# 3_InfoPerif.net
KiCad netlist of a schematic drawn in Altium Designer
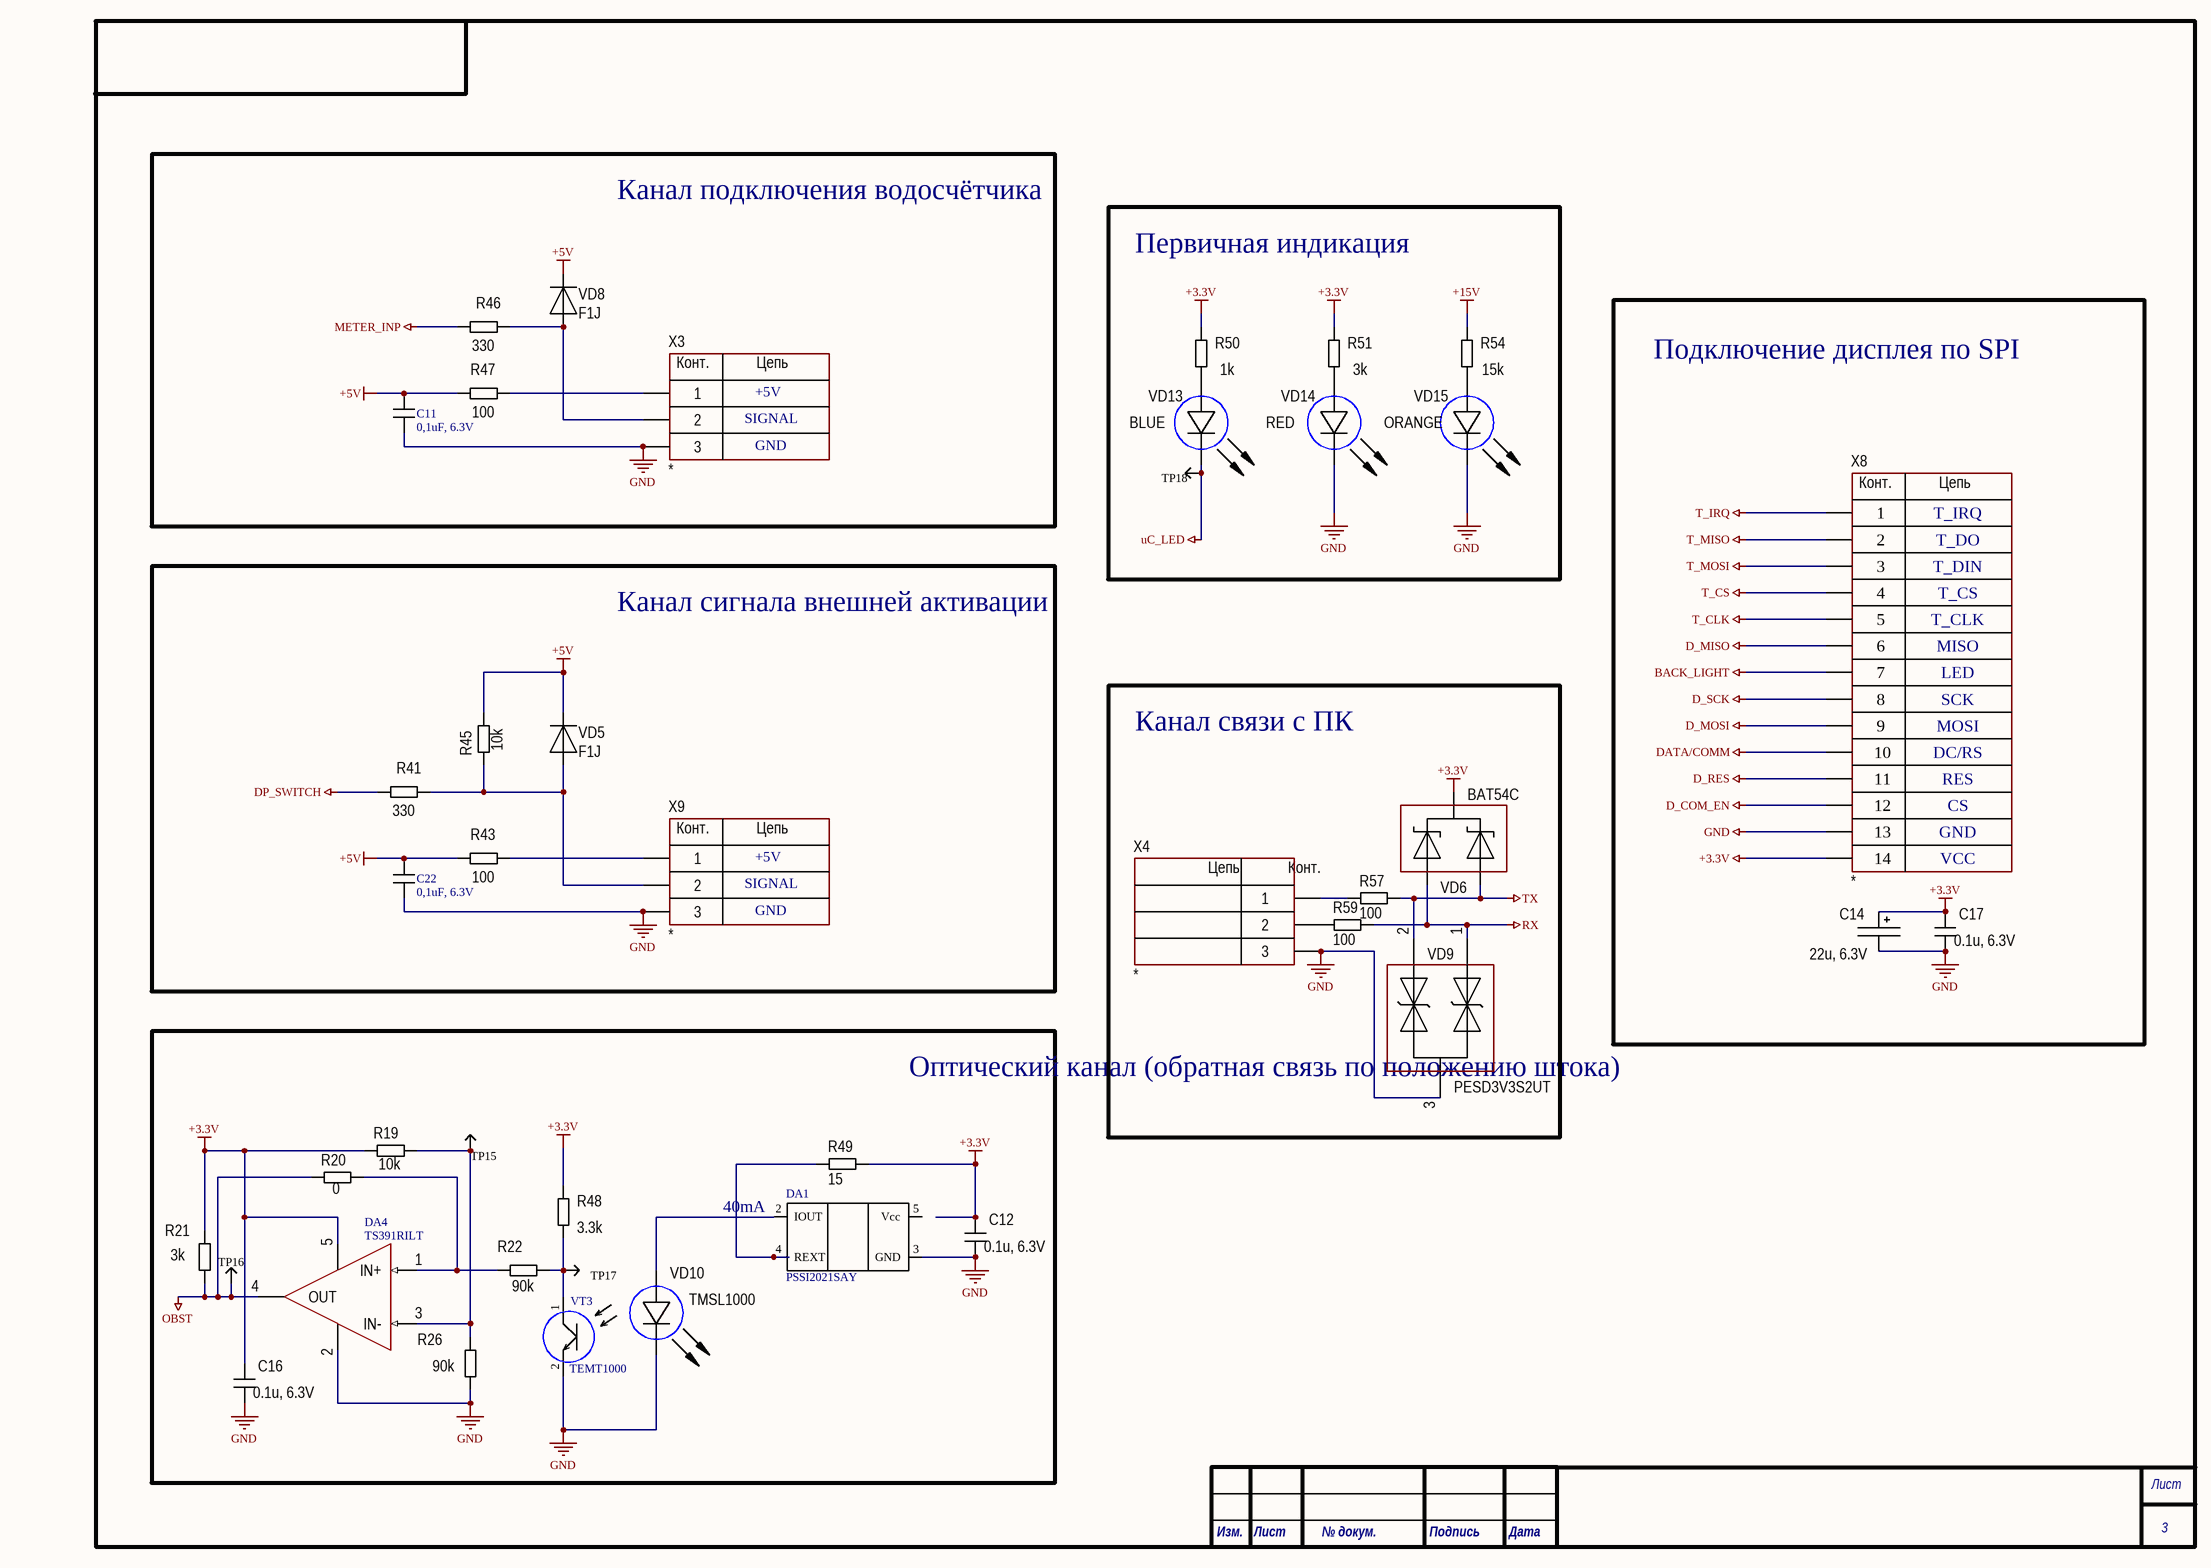
[diagram p0: 3_InfoPerif.SchDoc]

(export (version "E")
  (design (tool "Eeschema 10.0.6"))
  (components
    (comp (ref "C11")
      (value "0,1uF, 6.3V")
      (footprint "C_0603")
      (libsource (lib "Condensators") (part "C_SMD"))
    )
    (comp (ref "C12")
      (value "0.1u, 6.3V")
      (footprint "CH0402C")
      (description "0805")
      (libsource (lib "Condensators") (part "Capacitor"))
    )
    (comp (ref "C14")
      (value "22u, 6.3V")
      (footprint "TANTAL_A")
      (libsource (lib "Condensators") (part "TantalCap"))
    )
    (comp (ref "C16")
      (value "0.1u, 6.3V")
      (footprint "CH0402C")
      (description "0805")
      (libsource (lib "Condensators") (part "Capacitor"))
    )
    (comp (ref "C17")
      (value "0.1u, 6.3V")
      (footprint "CH0402C")
      (libsource (lib "Condensators") (part "Capacitor"))
    )
    (comp (ref "C22")
      (value "0,1uF, 6.3V")
      (footprint "C_0603")
      (libsource (lib "Condensators") (part "C_SMD"))
    )
    (comp (ref "DA1")
      (value "PSSI2021SAY")
      (footprint "SOT353")
      (description "Iout = 0.617/Rext + 15 µA")
      (libsource (lib "MicroIC") (part "PSSI2021SAY"))
    )
    (comp (ref "DA4")
      (value "TS391RILT")
      (footprint "SOT23-5")
      (description "SOT23-5")
      (libsource (lib "MicroIC") (part "LMV331M5"))
    )
    (comp (ref "R19") (value "10k") (footprint "CH0402R") (libsource (lib "Resistors") (part "Resistor")))
    (comp (ref "R20") (value "0") (footprint "CH0402R") (libsource (lib "Resistors") (part "Resistor")))
    (comp (ref "R21") (value "3k") (footprint "CH0402R") (libsource (lib "Resistors") (part "Resistor")))
    (comp (ref "R22") (value "90k") (footprint "CH0402R") (libsource (lib "Resistors") (part "Resistor")))
    (comp (ref "R26") (value "90k") (footprint "CH0402R") (libsource (lib "Resistors") (part "Resistor")))
    (comp (ref "R41") (value "330") (footprint "CH0402R") (libsource (lib "Resistors") (part "Resistor")))
    (comp (ref "R43") (value "100") (footprint "CH0805R") (libsource (lib "Resistors") (part "Resistor")))
    (comp (ref "R45") (value "10k") (footprint "CH0603R") (libsource (lib "Resistors") (part "Resistor")))
    (comp (ref "R46") (value "330") (footprint "CH0402R") (libsource (lib "Resistors") (part "Resistor")))
    (comp (ref "R47") (value "100") (footprint "CH0805R") (libsource (lib "Resistors") (part "Resistor")))
    (comp (ref "R48")
      (value "3.3k")
      (footprint "CH0402R")
      (description "0805")
      (libsource (lib "Resistors") (part "Resistor"))
    )
    (comp (ref "R49")
      (value "15")
      (footprint "CH0805R")
      (description "0805")
      (libsource (lib "Resistors") (part "Resistor"))
    )
    (comp (ref "R50") (value "1k") (footprint "CH0805R") (libsource (lib "Resistors") (part "Resistor")))
    (comp (ref "R51") (value "3k") (footprint "CH0805R") (libsource (lib "Resistors") (part "Resistor")))
    (comp (ref "R54") (value "15k") (footprint "CH0805R") (libsource (lib "Resistors") (part "Resistor")))
    (comp (ref "R57") (value "100") (footprint "CH0402R") (libsource (lib "Resistors") (part "Resistor")))
    (comp (ref "R59") (value "100") (footprint "CH0402R") (libsource (lib "Resistors") (part "Resistor")))
    (comp (ref "TP15") (value "~") (footprint "TestPoint") (libsource (lib "Melochi") (part "TestPoint")))
    (comp (ref "TP16") (value "~") (footprint "TestPoint") (libsource (lib "Melochi") (part "TestPoint")))
    (comp (ref "TP17") (value "~") (footprint "TestPoint") (libsource (lib "Melochi") (part "TestPoint")))
    (comp (ref "TP18") (value "~") (footprint "TestPoint") (libsource (lib "Melochi") (part "TestPoint")))
    (comp (ref "VD5") (value "F1J") (footprint "SOD123F") (libsource (lib "Diods") (part "Diod")))
    (comp (ref "VD6")
      (value "BAT54C")
      (footprint "SOT23_123")
      (libsource (lib "Diods") (part "Diod Schottky Array v.1"))
    )
    (comp (ref "VD8") (value "F1J") (footprint "SOD123F") (libsource (lib "Diods") (part "Diod")))
    (comp (ref "VD9")
      (value "PESD3V3S2UT")
      (footprint "SOT23_132")
      (libsource (lib "Diods") (part "TVS Array"))
    )
    (comp (ref "VD10") (value "TMSL1000") (footprint "TSML1000") (libsource (lib "Diods") (part "LED_1")))
    (comp (ref "VD13") (value "BLUE") (footprint "CH0603LB") (libsource (lib "Diods") (part "LED_1")))
    (comp (ref "VD14") (value "RED") (footprint "CH0603LB") (libsource (lib "Diods") (part "LED_1")))
    (comp (ref "VD15") (value "ORANGE") (footprint "CH0603LB") (libsource (lib "Diods") (part "LED_1")))
    (comp (ref "VT3")
      (value "TEMT1000")
      (footprint "TEMT1000")
      (libsource (lib "Tranzistor") (part "TEMT1000"))
    )
    (comp (ref "X3")
      (value "*")
      (footprint "CON: MX-22-05-3031")
      (libsource (lib "Connectors") (part "3-Connector"))
    )
    (comp (ref "X4") (value "*") (footprint "CON: MX-22-05-3031") (libsource (lib "") (part "3-Connector_1")))
    (comp (ref "X8") (value "*") (footprint "DS1024-14") (libsource (lib "Connectors") (part "14-Connector")))
    (comp (ref "X9")
      (value "*")
      (footprint "CON: MX-22-05-3031")
      (libsource (lib "Connectors") (part "3-Connector"))
    )
  )
  (nets
    (net (code "1") (name "+3.3V") (class "Default")
      (node (ref "C12") (pin "2") (pinfunction "2_2") (pintype "passive"))
      (node (ref "C14") (pin "1") (pinfunction "1_1") (pintype "power_in"))
      (node (ref "C16") (pin "2") (pinfunction "2_2") (pintype "passive"))
      (node (ref "C17") (pin "2") (pinfunction "2_2") (pintype "passive"))
      (node (ref "DA4") (pin "5") (pinfunction "V+_5") (pintype "power_in"))
      (node (ref "R19") (pin "2") (pinfunction "2_2") (pintype "passive"))
      (node (ref "R21") (pin "2") (pinfunction "2_2") (pintype "passive"))
      (node (ref "R48") (pin "2") (pinfunction "2_2") (pintype "passive"))
      (node (ref "R49") (pin "2") (pinfunction "2_2") (pintype "passive"))
      (node (ref "R50") (pin "2") (pinfunction "2_2") (pintype "passive"))
      (node (ref "R51") (pin "2") (pinfunction "2_2") (pintype "passive"))
      (node (ref "VD6") (pin "2") (pinfunction "2_2") (pintype "passive"))
      (node (ref "X8") (pin "14") (pinfunction "14_14") (pintype "power_in"))
    )
    (net (code "2") (name "+5V") (class "Default")
      (node (ref "C11") (pin "2") (pinfunction "2_2") (pintype "passive"))
      (node (ref "C22") (pin "2") (pinfunction "2_2") (pintype "passive"))
      (node (ref "R43") (pin "1") (pinfunction "1_1") (pintype "passive"))
      (node (ref "R45") (pin "1") (pinfunction "1_1") (pintype "passive"))
      (node (ref "R47") (pin "1") (pinfunction "1_1") (pintype "passive"))
      (node (ref "VD5") (pin "2") (pinfunction "2_2") (pintype "passive"))
      (node (ref "VD8") (pin "2") (pinfunction "2_2") (pintype "passive"))
    )
    (net (code "3") (name "+15V") (class "Default")
      (node (ref "R54") (pin "2") (pinfunction "2_2") (pintype "passive"))
    )
    (net (code "4") (name "BACK_LIGHT") (class "Default")
      (node (ref "X8") (pin "7") (pinfunction "7_7") (pintype "power_in"))
    )
    (net (code "5") (name "DATA{slash}COMM") (class "Default")
      (node (ref "X8") (pin "10") (pinfunction "10_10") (pintype "power_in"))
    )
    (net (code "6") (name "DP_SWITCH") (class "Default")
      (node (ref "R41") (pin "1") (pinfunction "1_1") (pintype "passive"))
    )
    (net (code "7") (name "D_COM_EN") (class "Default")
      (node (ref "X8") (pin "12") (pinfunction "12_12") (pintype "power_in"))
    )
    (net (code "8") (name "D_MISO") (class "Default")
      (node (ref "X8") (pin "6") (pinfunction "6_6") (pintype "power_in"))
    )
    (net (code "9") (name "D_MOSI") (class "Default")
      (node (ref "X8") (pin "9") (pinfunction "9_9") (pintype "power_in"))
    )
    (net (code "10") (name "D_RES") (class "Default")
      (node (ref "X8") (pin "11") (pinfunction "11_11") (pintype "power_in"))
    )
    (net (code "11") (name "D_SCK") (class "Default")
      (node (ref "X8") (pin "8") (pinfunction "8_8") (pintype "power_in"))
    )
    (net (code "12") (name "GND") (class "Default")
      (node (ref "C11") (pin "1") (pinfunction "1_1") (pintype "passive"))
      (node (ref "C12") (pin "1") (pinfunction "1_1") (pintype "passive"))
      (node (ref "C14") (pin "2") (pinfunction "2_2") (pintype "power_in"))
      (node (ref "C16") (pin "1") (pinfunction "1_1") (pintype "passive"))
      (node (ref "C17") (pin "1") (pinfunction "1_1") (pintype "passive"))
      (node (ref "C22") (pin "1") (pinfunction "1_1") (pintype "passive"))
      (node (ref "DA1") (pin "3") (pinfunction "GND_3") (pintype "passive"))
      (node (ref "DA4") (pin "2") (pinfunction "V-_2") (pintype "power_in"))
      (node (ref "R26") (pin "1") (pinfunction "1_1") (pintype "passive"))
      (node (ref "VD10") (pin "2") (pinfunction "C_2") (pintype "passive"))
      (node (ref "VD14") (pin "2") (pinfunction "C_2") (pintype "passive"))
      (node (ref "VD15") (pin "2") (pinfunction "C_2") (pintype "passive"))
      (node (ref "VD9") (pin "3") (pintype "passive"))
      (node (ref "VT3") (pin "2") (pinfunction "2_2") (pintype "passive"))
      (node (ref "X3") (pin "3") (pinfunction "3_3") (pintype "passive"))
      (node (ref "X4") (pin "3") (pinfunction "3_3") (pintype "passive"))
      (node (ref "X8") (pin "13") (pinfunction "13_13") (pintype "power_in"))
      (node (ref "X9") (pin "3") (pinfunction "3_3") (pintype "passive"))
    )
    (net (code "13") (name "METER_INP") (class "Default")
      (node (ref "R46") (pin "1") (pinfunction "1_1") (pintype "passive"))
    )
    (net (code "14") (name "Net-(DA1-IOUT)") (class "Default")
      (node (ref "DA1") (pin "2") (pinfunction "IOUT_2") (pintype "passive"))
      (node (ref "VD10") (pin "1") (pinfunction "A_1") (pintype "passive"))
    )
    (net (code "15") (name "Net-(DA1-REXT)") (class "Default")
      (node (ref "DA1") (pin "4") (pinfunction "REXT_4") (pintype "passive"))
      (node (ref "R49") (pin "1") (pinfunction "1_1") (pintype "passive"))
    )
    (net (code "16") (name "Net-(DA4-IN+)") (class "Default")
      (node (ref "DA4") (pin "1") (pinfunction "IN+_1") (pintype "input"))
      (node (ref "R20") (pin "1") (pinfunction "1_1") (pintype "passive"))
      (node (ref "R22") (pin "2") (pinfunction "2_2") (pintype "passive"))
    )
    (net (code "17") (name "Net-(DA4-IN-)") (class "Default")
      (node (ref "DA4") (pin "3") (pinfunction "IN-_3") (pintype "input"))
      (node (ref "R19") (pin "1") (pinfunction "1_1") (pintype "passive"))
      (node (ref "R26") (pin "2") (pinfunction "2_2") (pintype "passive"))
      (node (ref "TP15") (pin "0") (pinfunction "0_0") (pintype "passive"))
    )
    (net (code "18") (name "Net-(R22-Pad1)") (class "Default")
      (node (ref "R22") (pin "1") (pinfunction "1_1") (pintype "passive"))
      (node (ref "R48") (pin "1") (pinfunction "1_1") (pintype "passive"))
      (node (ref "TP17") (pin "0") (pinfunction "0_0") (pintype "passive"))
      (node (ref "VT3") (pin "1") (pinfunction "1_1") (pintype "passive"))
    )
    (net (code "19") (name "Net-(R41-Pad2)") (class "Default")
      (node (ref "R41") (pin "2") (pinfunction "2_2") (pintype "passive"))
      (node (ref "R45") (pin "2") (pinfunction "2_2") (pintype "passive"))
      (node (ref "VD5") (pin "1") (pinfunction "1_1") (pintype "passive"))
      (node (ref "X9") (pin "2") (pinfunction "2_2") (pintype "passive"))
    )
    (net (code "20") (name "Net-(R43-Pad2)") (class "Default")
      (node (ref "R43") (pin "2") (pinfunction "2_2") (pintype "passive"))
      (node (ref "X9") (pin "1") (pinfunction "1_1") (pintype "passive"))
    )
    (net (code "21") (name "Net-(R46-Pad2)") (class "Default")
      (node (ref "R46") (pin "2") (pinfunction "2_2") (pintype "passive"))
      (node (ref "VD8") (pin "1") (pinfunction "1_1") (pintype "passive"))
      (node (ref "X3") (pin "2") (pinfunction "2_2") (pintype "passive"))
    )
    (net (code "22") (name "Net-(R47-Pad2)") (class "Default")
      (node (ref "R47") (pin "2") (pinfunction "2_2") (pintype "passive"))
      (node (ref "X3") (pin "1") (pinfunction "1_1") (pintype "passive"))
    )
    (net (code "23") (name "Net-(R57-Pad1)") (class "Default")
      (node (ref "R57") (pin "1") (pinfunction "1_1") (pintype "passive"))
      (node (ref "X4") (pin "1") (pinfunction "1_1") (pintype "passive"))
    )
    (net (code "24") (name "Net-(R59-Pad1)") (class "Default")
      (node (ref "R59") (pin "1") (pinfunction "1_1") (pintype "passive"))
      (node (ref "X4") (pin "2") (pinfunction "2_2") (pintype "passive"))
    )
    (net (code "25") (name "Net-(VD13-A)") (class "Default")
      (node (ref "R50") (pin "1") (pinfunction "1_1") (pintype "passive"))
      (node (ref "VD13") (pin "1") (pinfunction "A_1") (pintype "passive"))
    )
    (net (code "26") (name "Net-(VD14-A)") (class "Default")
      (node (ref "R51") (pin "1") (pinfunction "1_1") (pintype "passive"))
      (node (ref "VD14") (pin "1") (pinfunction "A_1") (pintype "passive"))
    )
    (net (code "27") (name "Net-(VD15-A)") (class "Default")
      (node (ref "R54") (pin "1") (pinfunction "1_1") (pintype "passive"))
      (node (ref "VD15") (pin "1") (pinfunction "A_1") (pintype "passive"))
    )
    (net (code "28") (name "OBST") (class "Default")
      (node (ref "DA4") (pin "4") (pinfunction "OUT_4") (pintype "power_in"))
      (node (ref "R20") (pin "2") (pinfunction "2_2") (pintype "passive"))
      (node (ref "R21") (pin "1") (pinfunction "1_1") (pintype "passive"))
      (node (ref "TP16") (pin "0") (pinfunction "0_0") (pintype "passive"))
    )
    (net (code "29") (name "RX") (class "Default")
      (node (ref "R59") (pin "2") (pinfunction "2_2") (pintype "passive"))
      (node (ref "VD6") (pin "3") (pinfunction "3_3") (pintype "passive"))
      (node (ref "VD9") (pin "1") (pintype "passive"))
    )
    (net (code "30") (name "TX") (class "Default")
      (node (ref "R57") (pin "2") (pinfunction "2_2") (pintype "passive"))
      (node (ref "VD6") (pin "1") (pinfunction "1_1") (pintype "passive"))
      (node (ref "VD9") (pin "2") (pintype "passive"))
    )
    (net (code "31") (name "T_CLK") (class "Default")
      (node (ref "X8") (pin "5") (pinfunction "5_5") (pintype "power_in"))
    )
    (net (code "32") (name "T_CS") (class "Default")
      (node (ref "X8") (pin "4") (pinfunction "4_4") (pintype "power_in"))
    )
    (net (code "33") (name "T_IRQ") (class "Default")
      (node (ref "X8") (pin "1") (pinfunction "1_1") (pintype "passive"))
    )
    (net (code "34") (name "T_MISO") (class "Default")
      (node (ref "X8") (pin "2") (pinfunction "2_2") (pintype "passive"))
    )
    (net (code "35") (name "T_MOSI") (class "Default")
      (node (ref "X8") (pin "3") (pinfunction "3_3") (pintype "power_in"))
    )
    (net (code "36") (name "uC_LED") (class "Default")
      (node (ref "TP18") (pin "0") (pinfunction "0_0") (pintype "passive"))
      (node (ref "VD13") (pin "2") (pinfunction "C_2") (pintype "passive"))
    )
    (net (code "37") (name "unconnected-(DA1-Vcc-Pad5)") (class "Default")
      (node (ref "DA1") (pin "5") (pinfunction "Vcc_5") (pintype "passive"))
    )
  )
)
